# Main_board_rev21_top_image.net
KiCad netlist of a schematic drawn in EAGLE
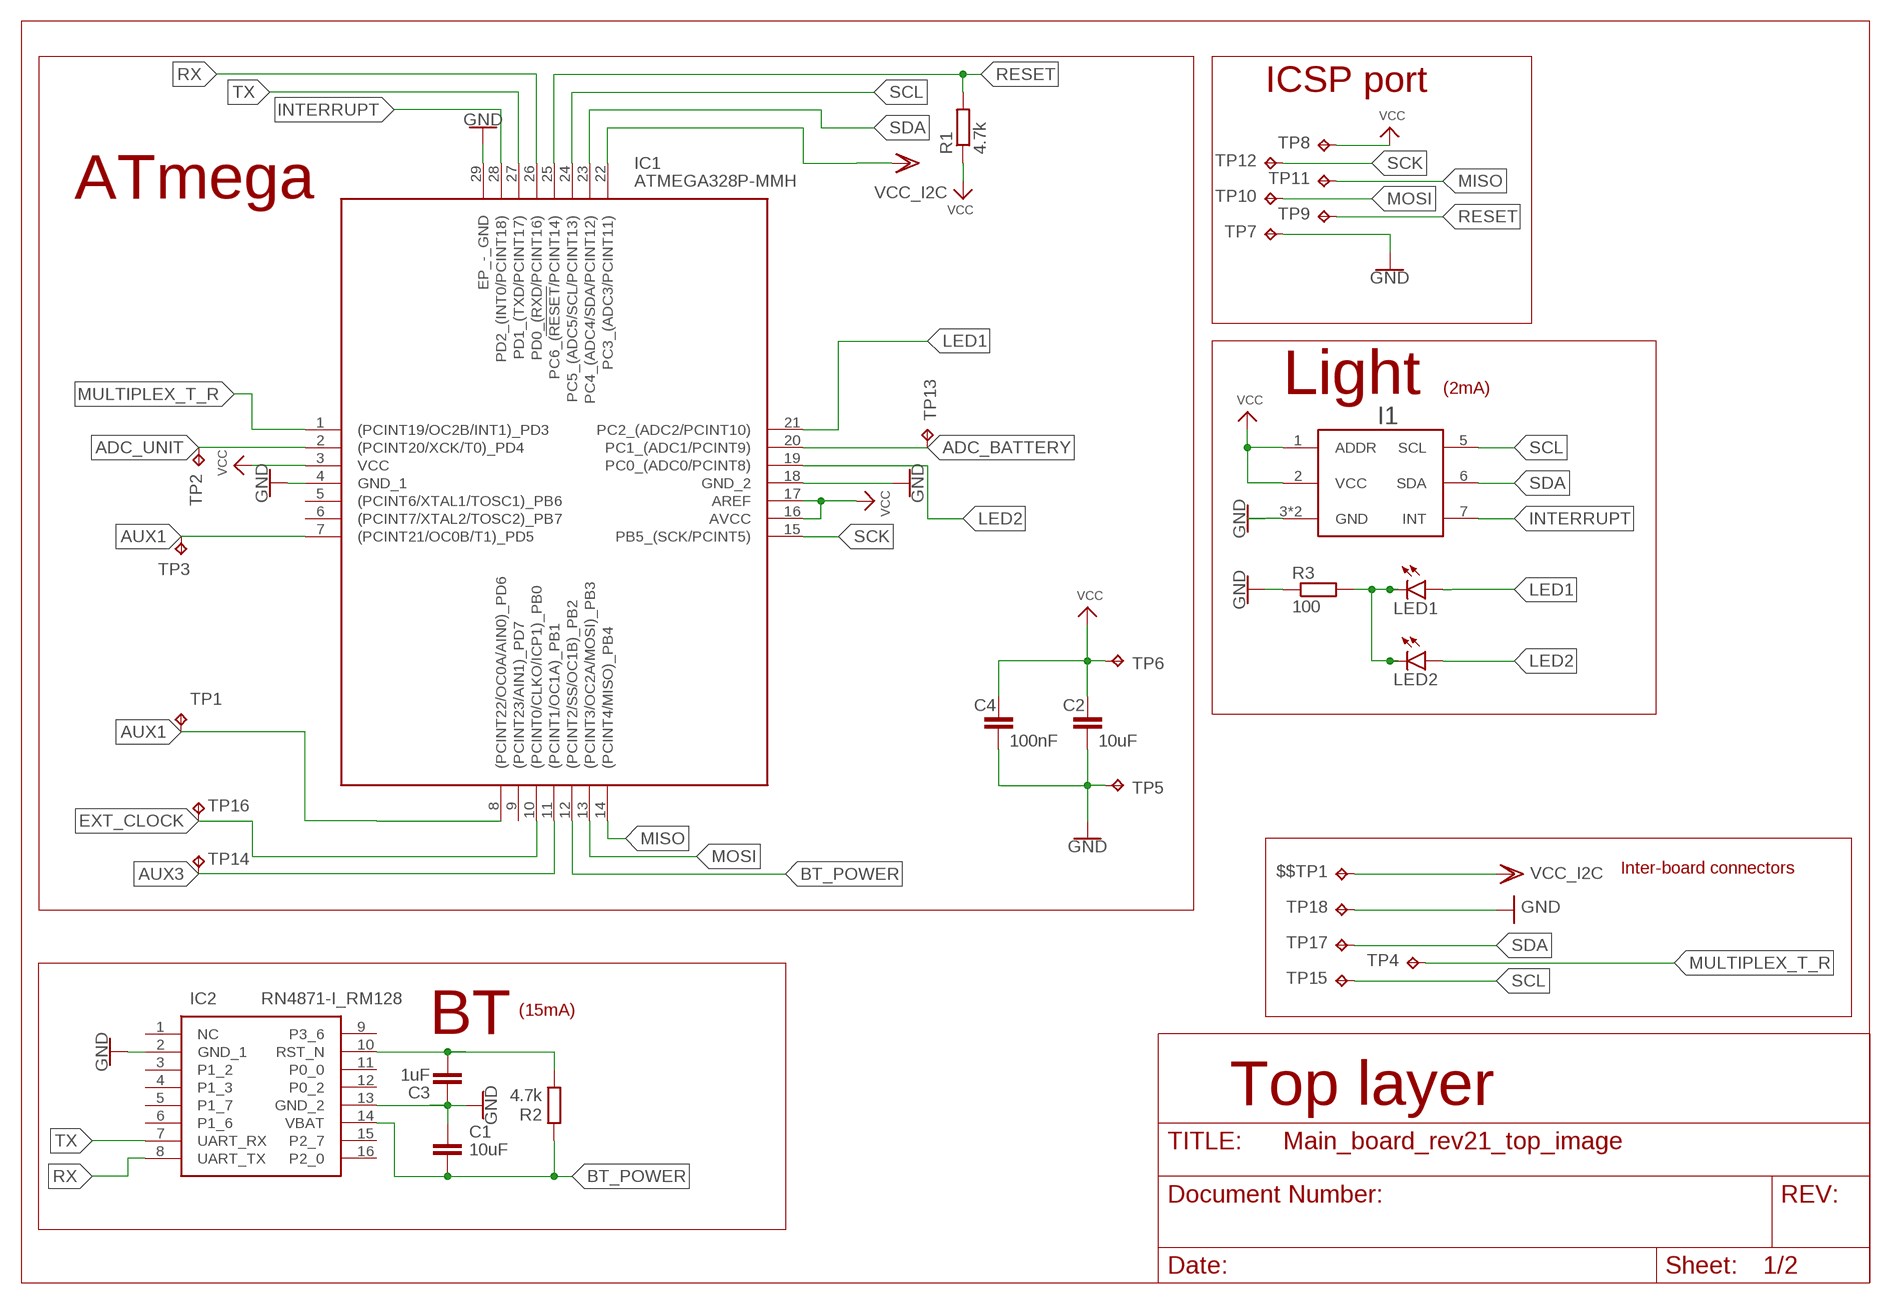
[diagram p0: schematic, sheet 1]

(export (version "E")
  (design (tool "Eeschema 10.0.6"))
  (components
    (comp (ref "$$TP1")
      (value "TP")
      (footprint "eagle-import:TEST_PAD_1MM")
      (libsource (lib "eagle-import") (part "TP"))
    )
    (comp (ref "C1")
      (value "10uF")
      (footprint "eagle-import:C0603K")
      (libsource (lib "eagle-import") (part "C-EUC0603K"))
    )
    (comp (ref "C2")
      (value "10uF")
      (footprint "eagle-import:C0603K")
      (libsource (lib "eagle-import") (part "C-EUC0603K"))
    )
    (comp (ref "C3")
      (value "1uF")
      (footprint "eagle-import:C0603K")
      (libsource (lib "eagle-import") (part "C-EUC0603K"))
    )
    (comp (ref "C4")
      (value "100nF")
      (footprint "eagle-import:C0603K")
      (libsource (lib "eagle-import") (part "C-EUC0603K"))
    )
    (comp (ref "I1")
      (value "BH1745NUC")
      (footprint "eagle-import:WSON008X2120")
      (libsource (lib "eagle-import") (part "BH1745NUC"))
    )
    (comp (ref "IC1")
      (value "ATMEGA328P-MMH")
      (footprint "eagle-import:QFN45P400X400X100-29N")
      (fields (field (name "MOUSER_PART_NUMBER") "556-ATMEGA328P-MMH"))
      (libsource (lib "eagle-import") (part "ATMEGA328P-MMH"))
    )
    (comp (ref "IC2")
      (value "RN4871-I_RM128")
      (footprint "eagle-import:RN4871")
      (fields
        (field (name "MANUFACTURER_PART_NUMBER") "RN4871-I/RM128")
        (field (name "MOUSER_PART_NUMBER") "579-RN4871-I/RM128")
      )
      (libsource (lib "eagle-import") (part "RN4871-I_RM128"))
    )
    (comp (ref "LED1")
      (value "LEDCHIPLED_0603")
      (footprint "eagle-import:CHIPLED_0603")
      (libsource (lib "eagle-import") (part "LEDCHIPLED_0603"))
    )
    (comp (ref "LED2")
      (value "LEDCHIPLED_0603")
      (footprint "eagle-import:CHIPLED_0603")
      (libsource (lib "eagle-import") (part "LEDCHIPLED_0603"))
    )
    (comp (ref "R1")
      (value "4.7k")
      (footprint "eagle-import:R0603")
      (libsource (lib "eagle-import") (part "R-EU_R0603"))
    )
    (comp (ref "R2")
      (value "4.7k")
      (footprint "eagle-import:R0603")
      (libsource (lib "eagle-import") (part "R-EU_R0603"))
    )
    (comp (ref "R3")
      (value "100")
      (footprint "eagle-import:R0603")
      (libsource (lib "eagle-import") (part "R-EU_R0603"))
    )
    (comp (ref "TP1")
      (value "TP")
      (footprint "eagle-import:TEST_PAD_1MM")
      (libsource (lib "eagle-import") (part "TP"))
    )
    (comp (ref "TP2")
      (value "TP")
      (footprint "eagle-import:TEST_PAD_1MM")
      (libsource (lib "eagle-import") (part "TP"))
    )
    (comp (ref "TP3")
      (value "TP")
      (footprint "eagle-import:TEST_PAD_1MM")
      (libsource (lib "eagle-import") (part "TP"))
    )
    (comp (ref "TP4")
      (value "TP")
      (footprint "eagle-import:TEST_PAD_1MM")
      (libsource (lib "eagle-import") (part "TP"))
    )
    (comp (ref "TP5")
      (value "TP")
      (footprint "eagle-import:TEST_PAD_1MM")
      (libsource (lib "eagle-import") (part "TP"))
    )
    (comp (ref "TP6")
      (value "TP")
      (footprint "eagle-import:TEST_PAD_1MM")
      (libsource (lib "eagle-import") (part "TP"))
    )
    (comp (ref "TP7")
      (value "TPTP09SQ")
      (footprint "eagle-import:TP09SQ")
      (libsource (lib "eagle-import") (part "TPTP09SQ"))
    )
    (comp (ref "TP8")
      (value "TPTP09SQ")
      (footprint "eagle-import:TP09SQ")
      (libsource (lib "eagle-import") (part "TPTP09SQ"))
    )
    (comp (ref "TP9")
      (value "TPTP09SQ")
      (footprint "eagle-import:TP09SQ")
      (libsource (lib "eagle-import") (part "TPTP09SQ"))
    )
    (comp (ref "TP10")
      (value "TPTP09SQ")
      (footprint "eagle-import:TP09SQ")
      (libsource (lib "eagle-import") (part "TPTP09SQ"))
    )
    (comp (ref "TP11")
      (value "TPTP09SQ")
      (footprint "eagle-import:TP09SQ")
      (libsource (lib "eagle-import") (part "TPTP09SQ"))
    )
    (comp (ref "TP12")
      (value "TPTP09SQ")
      (footprint "eagle-import:TP09SQ")
      (libsource (lib "eagle-import") (part "TPTP09SQ"))
    )
    (comp (ref "TP13")
      (value "TP")
      (footprint "eagle-import:TEST_PAD_1MM")
      (libsource (lib "eagle-import") (part "TP"))
    )
    (comp (ref "TP14")
      (value "TP")
      (footprint "eagle-import:TEST_PAD_1MM")
      (libsource (lib "eagle-import") (part "TP"))
    )
    (comp (ref "TP15")
      (value "TP")
      (footprint "eagle-import:TEST_PAD_1MM")
      (libsource (lib "eagle-import") (part "TP"))
    )
    (comp (ref "TP16")
      (value "TP")
      (footprint "eagle-import:TEST_PAD_1MM")
      (libsource (lib "eagle-import") (part "TP"))
    )
    (comp (ref "TP17")
      (value "TP")
      (footprint "eagle-import:TEST_PAD_1MM")
      (libsource (lib "eagle-import") (part "TP"))
    )
    (comp (ref "TP18")
      (value "TP")
      (footprint "eagle-import:TEST_PAD_1MM")
      (libsource (lib "eagle-import") (part "TP"))
    )
  )
  (nets
    (net (code "1") (name "ADC_BATTERY") (class "Default")
      (node (ref "IC1") (pin "20") (pinfunction "PC1_(ADC1/PCINT9)_20") (pintype "bidirectional"))
      (node (ref "TP13") (pin "P$1") (pinfunction "TP_P$1") (pintype "input"))
    )
    (net (code "2") (name "ADC_UNIT") (class "Default")
      (node (ref "IC1") (pin "2") (pinfunction "(PCINT20/XCK/T0)_PD4_2") (pintype "bidirectional"))
      (node (ref "TP2") (pin "P$1") (pinfunction "TP_P$1") (pintype "input"))
    )
    (net (code "3") (name "AUX1") (class "Default")
      (node (ref "IC1") (pin "7") (pinfunction "(PCINT21/OC0B/T1)_PD5_7") (pintype "bidirectional"))
      (node (ref "TP3") (pin "P$1") (pinfunction "TP_P$1") (pintype "input"))
    )
    (net (code "4") (name "AUX3") (class "Default")
      (node (ref "IC1") (pin "11") (pinfunction "(PCINT1/OC1A)_PB1_11") (pintype "bidirectional"))
      (node (ref "TP14") (pin "P$1") (pinfunction "TP_P$1") (pintype "input"))
    )
    (net (code "5") (name "BT_POWER") (class "Default")
      (node (ref "C1") (pin "1") (pinfunction "1_1") (pintype "passive"))
      (node (ref "IC1") (pin "12") (pinfunction "(PCINT2/SS/OC1B)_PB2_12") (pintype "bidirectional"))
      (node (ref "IC2") (pin "14") (pinfunction "VBAT_14") (pintype "bidirectional"))
      (node (ref "R2") (pin "2") (pinfunction "2_2") (pintype "passive"))
    )
    (net (code "6") (name "EXT_CLOCK") (class "Default")
      (node (ref "IC1") (pin "10") (pinfunction "(PCINT0/CLKO/ICP1)_PB0_10") (pintype "bidirectional"))
      (node (ref "TP16") (pin "P$1") (pinfunction "TP_P$1") (pintype "input"))
    )
    (net (code "7") (name "GND") (class "Default")
      (node (ref "C1") (pin "2") (pinfunction "2_2") (pintype "passive"))
      (node (ref "C2") (pin "2") (pinfunction "2_2") (pintype "passive"))
      (node (ref "C3") (pin "1") (pinfunction "1_1") (pintype "passive"))
      (node (ref "C4") (pin "2") (pinfunction "2_2") (pintype "passive"))
      (node (ref "I1") (pin "3") (pinfunction "GND_3") (pintype "bidirectional"))
      (node (ref "I1") (pin "4") (pinfunction "GND_4") (pintype "bidirectional"))
      (node (ref "IC1") (pin "18") (pinfunction "GND_2_18") (pintype "bidirectional"))
      (node (ref "IC1") (pin "29") (pinfunction "EP_-_GND_29") (pintype "bidirectional"))
      (node (ref "IC1") (pin "4") (pinfunction "GND_1_4") (pintype "bidirectional"))
      (node (ref "IC2") (pin "13") (pinfunction "GND_2_13") (pintype "bidirectional"))
      (node (ref "IC2") (pin "2") (pinfunction "GND_1_2") (pintype "bidirectional"))
      (node (ref "R3") (pin "1") (pinfunction "1_1") (pintype "passive"))
      (node (ref "TP18") (pin "P$1") (pinfunction "TP_P$1") (pintype "input"))
      (node (ref "TP5") (pin "P$1") (pinfunction "TP_P$1") (pintype "input"))
      (node (ref "TP7") (pin "TP") (pinfunction "TP_TP") (pintype "input"))
    )
    (net (code "8") (name "INTERRUPT") (class "Default")
      (node (ref "I1") (pin "7") (pinfunction "INT_7") (pintype "bidirectional"))
      (node (ref "IC1") (pin "28") (pinfunction "PD2_(INT0/PCINT18)_28") (pintype "bidirectional"))
    )
    (net (code "9") (name "LED1") (class "Default")
      (node (ref "IC1") (pin "21") (pinfunction "PC2_(ADC2/PCINT10)_21") (pintype "bidirectional"))
      (node (ref "LED1") (pin "A") (pinfunction "A_A") (pintype "passive"))
    )
    (net (code "10") (name "LED2") (class "Default")
      (node (ref "IC1") (pin "19") (pinfunction "PC0_(ADC0/PCINT8)_19") (pintype "bidirectional"))
      (node (ref "LED2") (pin "A") (pinfunction "A_A") (pintype "passive"))
    )
    (net (code "11") (name "MISO") (class "Default")
      (node (ref "IC1") (pin "14") (pinfunction "(PCINT4/MISO)_PB4_14") (pintype "bidirectional"))
      (node (ref "TP11") (pin "TP") (pinfunction "TP_TP") (pintype "input"))
    )
    (net (code "12") (name "MOSI") (class "Default")
      (node (ref "IC1") (pin "13") (pinfunction "(PCINT3/OC2A/MOSI)_PB3_13") (pintype "bidirectional"))
      (node (ref "TP10") (pin "TP") (pinfunction "TP_TP") (pintype "input"))
    )
    (net (code "13") (name "MULTIPLEX_T_R") (class "Default")
      (node (ref "IC1") (pin "1") (pinfunction "(PCINT19/OC2B/INT1)_PD3_1") (pintype "bidirectional"))
      (node (ref "TP4") (pin "P$1") (pinfunction "TP_P$1") (pintype "input"))
    )
    (net (code "14") (name "Net-(IC1-(PCINT22{slash}OC0A{slash}AIN0)_PD6)") (class "Default")
      (node (ref "IC1") (pin "8") (pinfunction "(PCINT22/OC0A/AIN0)_PD6_8") (pintype "bidirectional"))
      (node (ref "TP1") (pin "P$1") (pinfunction "TP_P$1") (pintype "input"))
    )
    (net (code "15") (name "Net-(IC2-RST_N)") (class "Default")
      (node (ref "C3") (pin "2") (pinfunction "2_2") (pintype "passive"))
      (node (ref "IC2") (pin "10") (pinfunction "RST_N_10") (pintype "bidirectional"))
      (node (ref "R2") (pin "1") (pinfunction "1_1") (pintype "passive"))
    )
    (net (code "16") (name "Net-(LED1-PadC)") (class "Default")
      (node (ref "LED1") (pin "C") (pinfunction "C_C") (pintype "passive"))
      (node (ref "LED2") (pin "C") (pinfunction "C_C") (pintype "passive"))
      (node (ref "R3") (pin "2") (pinfunction "2_2") (pintype "passive"))
    )
    (net (code "17") (name "RESET") (class "Default")
      (node (ref "IC1") (pin "25") (pinfunction "PC6_(~{RESET}/PCINT14)_25") (pintype "bidirectional"))
      (node (ref "R1") (pin "2") (pinfunction "2_2") (pintype "passive"))
      (node (ref "TP9") (pin "TP") (pinfunction "TP_TP") (pintype "input"))
    )
    (net (code "18") (name "RX") (class "Default")
      (node (ref "IC1") (pin "26") (pinfunction "PD0_(RXD/PCINT16)_26") (pintype "bidirectional"))
      (node (ref "IC2") (pin "8") (pinfunction "UART_TX_8") (pintype "bidirectional"))
    )
    (net (code "19") (name "SCK") (class "Default")
      (node (ref "IC1") (pin "15") (pinfunction "PB5_(SCK/PCINT5)_15") (pintype "bidirectional"))
      (node (ref "TP12") (pin "TP") (pinfunction "TP_TP") (pintype "input"))
    )
    (net (code "20") (name "SCL") (class "Default")
      (node (ref "I1") (pin "5") (pinfunction "SCL_5") (pintype "bidirectional"))
      (node (ref "IC1") (pin "24") (pinfunction "PC5_(ADC5/SCL/PCINT13)_24") (pintype "bidirectional"))
      (node (ref "TP15") (pin "P$1") (pinfunction "TP_P$1") (pintype "input"))
    )
    (net (code "21") (name "SDA") (class "Default")
      (node (ref "I1") (pin "6") (pinfunction "SDA_6") (pintype "bidirectional"))
      (node (ref "IC1") (pin "23") (pinfunction "PC4_(ADC4/SDA/PCINT12)_23") (pintype "bidirectional"))
      (node (ref "TP17") (pin "P$1") (pinfunction "TP_P$1") (pintype "input"))
    )
    (net (code "22") (name "TX") (class "Default")
      (node (ref "IC1") (pin "27") (pinfunction "PD1_(TXD/PCINT17)_27") (pintype "bidirectional"))
      (node (ref "IC2") (pin "7") (pinfunction "UART_RX_7") (pintype "bidirectional"))
    )
    (net (code "23") (name "VCC") (class "Default")
      (node (ref "C2") (pin "1") (pinfunction "1_1") (pintype "passive"))
      (node (ref "C4") (pin "1") (pinfunction "1_1") (pintype "passive"))
      (node (ref "I1") (pin "1") (pinfunction "ADDR_1") (pintype "bidirectional"))
      (node (ref "I1") (pin "2") (pinfunction "VCC_2") (pintype "bidirectional"))
      (node (ref "IC1") (pin "16") (pinfunction "AVCC_16") (pintype "bidirectional"))
      (node (ref "IC1") (pin "17") (pinfunction "AREF_17") (pintype "bidirectional"))
      (node (ref "IC1") (pin "3") (pinfunction "VCC_3") (pintype "bidirectional"))
      (node (ref "R1") (pin "1") (pinfunction "1_1") (pintype "passive"))
      (node (ref "TP6") (pin "P$1") (pinfunction "TP_P$1") (pintype "input"))
      (node (ref "TP8") (pin "TP") (pinfunction "TP_TP") (pintype "input"))
    )
    (net (code "24") (name "VDD") (class "Default")
      (node (ref "$$TP1") (pin "P$1") (pinfunction "TP_P$1") (pintype "input"))
      (node (ref "IC1") (pin "22") (pinfunction "PC3_(ADC3/PCINT11)_22") (pintype "bidirectional"))
    )
    (net (code "25") (name "unconnected-(IC1-(PCINT6{slash}XTAL1{slash}TOSC1)_PB6-Pad5)") (class "Default")
      (node (ref "IC1") (pin "5") (pinfunction "(PCINT6/XTAL1/TOSC1)_PB6_5") (pintype "bidirectional"))
    )
    (net (code "26") (name "unconnected-(IC1-(PCINT7{slash}XTAL2{slash}TOSC2)_PB7-Pad6)") (class "Default")
      (node (ref "IC1") (pin "6") (pinfunction "(PCINT7/XTAL2/TOSC2)_PB7_6") (pintype "bidirectional"))
    )
    (net (code "27") (name "unconnected-(IC1-(PCINT23{slash}AIN1)_PD7-Pad9)") (class "Default")
      (node (ref "IC1") (pin "9") (pinfunction "(PCINT23/AIN1)_PD7_9") (pintype "bidirectional"))
    )
    (net (code "28") (name "unconnected-(IC2-NC-Pad1)") (class "Default")
      (node (ref "IC2") (pin "1") (pinfunction "NC_1") (pintype "no_connect"))
    )
    (net (code "29") (name "unconnected-(IC2-P0_0-Pad11)") (class "Default")
      (node (ref "IC2") (pin "11") (pinfunction "P0_0_11") (pintype "bidirectional"))
    )
    (net (code "30") (name "unconnected-(IC2-P0_2-Pad12)") (class "Default")
      (node (ref "IC2") (pin "12") (pinfunction "P0_2_12") (pintype "bidirectional"))
    )
    (net (code "31") (name "unconnected-(IC2-P1_2-Pad3)") (class "Default")
      (node (ref "IC2") (pin "3") (pinfunction "P1_2_3") (pintype "bidirectional"))
    )
    (net (code "32") (name "unconnected-(IC2-P1_3-Pad4)") (class "Default")
      (node (ref "IC2") (pin "4") (pinfunction "P1_3_4") (pintype "bidirectional"))
    )
    (net (code "33") (name "unconnected-(IC2-P1_6-Pad6)") (class "Default")
      (node (ref "IC2") (pin "6") (pinfunction "P1_6_6") (pintype "bidirectional"))
    )
    (net (code "34") (name "unconnected-(IC2-P1_7-Pad5)") (class "Default")
      (node (ref "IC2") (pin "5") (pinfunction "P1_7_5") (pintype "bidirectional"))
    )
    (net (code "35") (name "unconnected-(IC2-P2_0-Pad16)") (class "Default")
      (node (ref "IC2") (pin "16") (pinfunction "P2_0_16") (pintype "bidirectional"))
    )
    (net (code "36") (name "unconnected-(IC2-P2_7-Pad15)") (class "Default")
      (node (ref "IC2") (pin "15") (pinfunction "P2_7_15") (pintype "bidirectional"))
    )
    (net (code "37") (name "unconnected-(IC2-P3_6-Pad9)") (class "Default")
      (node (ref "IC2") (pin "9") (pinfunction "P3_6_9") (pintype "bidirectional"))
    )
  )
)
